# do_an2.net
KiCad netlist of a schematic drawn in Altium Designer
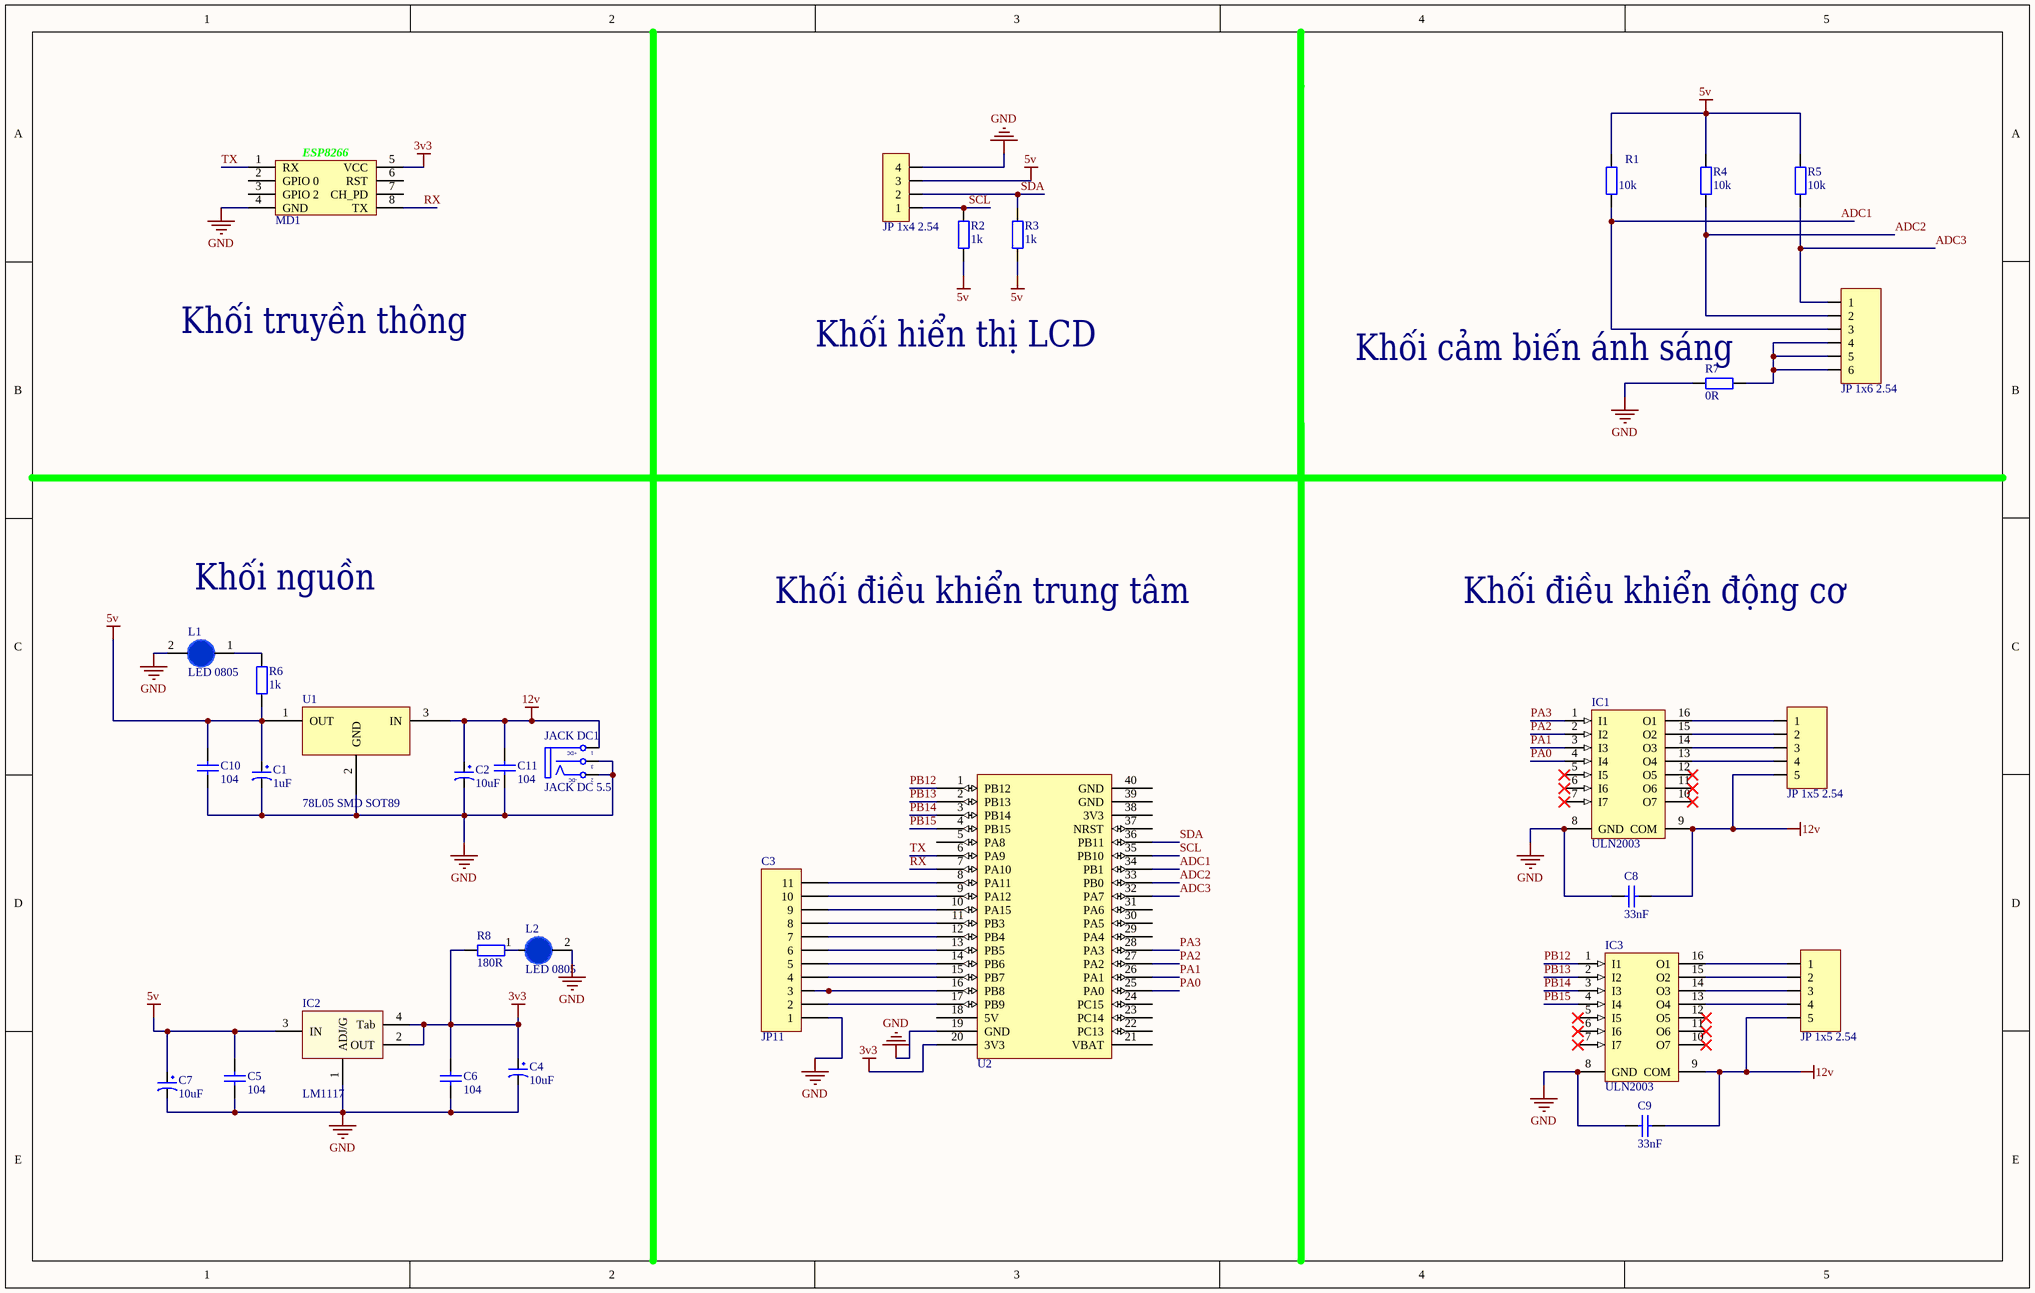
[diagram p0: do_an2.SchDoc]

(export (version "E")
  (design (tool "Eeschema 10.0.6"))
  (components
    (comp (ref "C1")
      (value "1uF")
      (footprint "tu hoa 5mm")
      (description "Cắm")
      (libsource (lib "Altium_Lib_by_KhueNguyenCreator") (part "Tu Hoa 1uF 50V 5x11"))
    )
    (comp (ref "C2")
      (value "10uF")
      (footprint "tu hoa 4mm")
      (description "Cắm")
      (libsource (lib "Altium_Lib_by_KhueNguyenCreator") (part "Tu Hoa 10uF 16V 4x7"))
    )
    (comp (ref "C3")
      (value "JP11")
      (footprint "JP11-C1T")
      (description "WR-PHD 2.54 mm Angled Socket Header")
      (fields
        (field (name "MANUFACTURER") "Würth Elektronik eiSos GmbH")
        (field (name "PARTNO") "613011143121")
        (field (name "CREATED BY") "Karrer Zheng")
      )
      (libsource (lib "My Library") (part "JP11"))
    )
    (comp (ref "C4")
      (value "10uF")
      (footprint "tu hoa 4mm")
      (description "Cắm")
      (libsource (lib "Altium_Lib_by_KhueNguyenCreator") (part "Tu Hoa 10uF 16V 4x7"))
    )
    (comp (ref "C5")
      (value "104")
      (footprint "tu 0805")
      (description "Dán")
      (libsource (lib "Altium_Lib_by_KhueNguyenCreator") (part "Tu 0805 104 50V 10%"))
    )
    (comp (ref "C6")
      (value "104")
      (footprint "tu 0805")
      (description "Dán")
      (libsource (lib "Altium_Lib_by_KhueNguyenCreator") (part "Tu 0805 104 50V 10%"))
    )
    (comp (ref "C7")
      (value "10uF")
      (footprint "tu hoa 4mm")
      (description "Cắm")
      (libsource (lib "Altium_Lib_by_KhueNguyenCreator") (part "Tu Hoa 10uF 16V 4x7"))
    )
    (comp (ref "C8")
      (value "33nF")
      (footprint "tu 0805")
      (description "Dán")
      (libsource (lib "Altium_Lib_by_KhueNguyenCreator") (part "Tu 0805 33nF 50V 20%"))
    )
    (comp (ref "C9")
      (value "33nF")
      (footprint "tu 0805")
      (description "Dán")
      (libsource (lib "Altium_Lib_by_KhueNguyenCreator") (part "Tu 0805 33nF 50V 20%"))
    )
    (comp (ref "C10")
      (value "104")
      (footprint "tu 0805")
      (description "Dán")
      (libsource (lib "Altium_Lib_by_KhueNguyenCreator") (part "Tu 0805 104 50V 10%"))
    )
    (comp (ref "C11")
      (value "104")
      (footprint "tu 0805")
      (description "Dán")
      (libsource (lib "Altium_Lib_by_KhueNguyenCreator") (part "Tu 0805 104 50V 10%"))
    )
    (comp (ref "IC1")
      (value "ULN2003")
      (footprint "SOP 16")
      (description "Dán")
      (libsource (lib "Altium_Lib_by_KhueNguyenCreator") (part "ULN2003A SMD"))
    )
    (comp (ref "IC2")
      (value "LM1117")
      (footprint "SOT223-4N")
      (description "3v3")
      (libsource (lib "My Library") (part "LM1117"))
    )
    (comp (ref "IC3")
      (value "ULN2003")
      (footprint "SOP 16")
      (description "Dán")
      (libsource (lib "Altium_Lib_by_KhueNguyenCreator") (part "ULN2003A SMD"))
    )
    (comp (ref "JACK DC1")
      (value "JACK DC 5.5")
      (footprint "JACK DC 5.5")
      (libsource (lib "Altium_Lib_by_KhueNguyenCreator") (part "JACK DC 5.5"))
    )
    (comp (ref "JP1")
      (value "JP 1x4 2.54")
      (footprint "JP 1x4 CC")
      (description "Cắm")
      (libsource (lib "Altium_Lib_by_KhueNguyenCreator") (part "JP 1x4 2.54 Cai Cong"))
    )
    (comp (ref "JP2")
      (value "JP 1x6 2.54")
      (footprint "JP 1x6 CT")
      (description "Cắm")
      (libsource (lib "Altium_Lib_by_KhueNguyenCreator") (part "JP 1x6 2.54 Cai Thang"))
    )
    (comp (ref "JP3")
      (value "JP 1x5 2.54")
      (footprint "JP 1x5 DT")
      (description "Cắm")
      (libsource (lib "Altium_Lib_by_KhueNguyenCreator") (part "JP 1x5 2.54 Duc Thang"))
    )
    (comp (ref "JP4")
      (value "JP 1x5 2.54")
      (footprint "JP 1x5 DT")
      (description "Cắm")
      (libsource (lib "Altium_Lib_by_KhueNguyenCreator") (part "JP 1x5 2.54 Duc Thang"))
    )
    (comp (ref "L1")
      (value "LED 0805")
      (footprint "LED-0805-Blue")
      (description "Dán")
      (libsource (lib "Altium_Lib_by_KhueNguyenCreator") (part "LED 0805 Xanh Duong"))
    )
    (comp (ref "L2")
      (value "LED 0805")
      (footprint "LED-0805-Blue")
      (description "Dán")
      (libsource (lib "Altium_Lib_by_KhueNguyenCreator") (part "LED 0805 Xanh Duong"))
    )
    (comp (ref "MD1")
      (value "ESP8266 Module")
      (footprint "ESP2866 Module")
      (libsource (lib "Altium_Lib_by_KhueNguyenCreator") (part "ESP8266 Module"))
    )
    (comp (ref "R1")
      (value "10k")
      (footprint "tro smd 0805")
      (description "Dán")
      (libsource (lib "Altium_Lib_by_KhueNguyenCreator") (part "Tro 0805 5% 10k"))
    )
    (comp (ref "R2")
      (value "1k")
      (footprint "tro smd 0805")
      (description "Dán")
      (libsource (lib "Altium_Lib_by_KhueNguyenCreator") (part "Tro 0805 1% 1k"))
    )
    (comp (ref "R3")
      (value "1k")
      (footprint "tro smd 0805")
      (description "Dán")
      (libsource (lib "Altium_Lib_by_KhueNguyenCreator") (part "Tro 0805 1% 1k"))
    )
    (comp (ref "R4")
      (value "10k")
      (footprint "tro smd 0805")
      (description "Dán")
      (libsource (lib "Altium_Lib_by_KhueNguyenCreator") (part "Tro 0805 5% 10k"))
    )
    (comp (ref "R5")
      (value "10k")
      (footprint "tro smd 0805")
      (description "Dán")
      (libsource (lib "Altium_Lib_by_KhueNguyenCreator") (part "Tro 0805 5% 10k"))
    )
    (comp (ref "R6")
      (value "1k")
      (footprint "tro smd 0805")
      (description "Dán")
      (libsource (lib "Altium_Lib_by_KhueNguyenCreator") (part "Tro 0805 5% 1k"))
    )
    (comp (ref "R7")
      (value "0R")
      (footprint "tro smd 0805")
      (description "Dán")
      (libsource (lib "Altium_Lib_by_KhueNguyenCreator") (part "Tro 0805 5% 0R"))
    )
    (comp (ref "R8")
      (value "180R")
      (footprint "tro smd 0805")
      (description "Dán")
      (libsource (lib "Altium_Lib_by_KhueNguyenCreator") (part "Tro 0805 5% 180R"))
    )
    (comp (ref "U1")
      (value "78L05 SMD SOT89")
      (footprint "SOT89")
      (description "Dán")
      (libsource (lib "Altium_Lib_by_KhueNguyenCreator") (part "78L05 SMD SOT89"))
    )
    (comp (ref "U2")
      (value "STM32 BluePill")
      (footprint "STM32 Bluepill")
      (description "STM32F103C8T6 breakout board")
      (libsource (lib "My Library") (part "STM32 BluePill"))
    )
  )
  (nets
    (net (code "1") (name "/ADC1") (class "Default")
      (node (ref "JP2") (pin "3") (pinfunction "3_3") (pintype "passive"))
      (node (ref "R1") (pin "1") (pinfunction "1_1") (pintype "passive"))
      (node (ref "U2") (pin "34") (pinfunction "PB1_34") (pintype "bidirectional"))
    )
    (net (code "2") (name "/ADC2") (class "Default")
      (node (ref "JP2") (pin "2") (pinfunction "2_2") (pintype "passive"))
      (node (ref "R4") (pin "1") (pinfunction "1_1") (pintype "passive"))
      (node (ref "U2") (pin "33") (pinfunction "PB0_33") (pintype "bidirectional"))
    )
    (net (code "3") (name "/ADC3") (class "Default")
      (node (ref "JP2") (pin "1") (pinfunction "1_1") (pintype "passive"))
      (node (ref "R5") (pin "1") (pinfunction "1_1") (pintype "passive"))
      (node (ref "U2") (pin "32") (pinfunction "PA7_32") (pintype "bidirectional"))
    )
    (net (code "4") (name "/PA0") (class "Default")
      (node (ref "IC1") (pin "4") (pinfunction "I4_4") (pintype "input"))
      (node (ref "U2") (pin "25") (pinfunction "PA0_25") (pintype "bidirectional"))
    )
    (net (code "5") (name "/PA1") (class "Default")
      (node (ref "IC1") (pin "3") (pinfunction "I3_3") (pintype "input"))
      (node (ref "U2") (pin "26") (pinfunction "PA1_26") (pintype "bidirectional"))
    )
    (net (code "6") (name "/PA2") (class "Default")
      (node (ref "IC1") (pin "2") (pinfunction "I2_2") (pintype "input"))
      (node (ref "U2") (pin "27") (pinfunction "PA2_27") (pintype "bidirectional"))
    )
    (net (code "7") (name "/PA3") (class "Default")
      (node (ref "IC1") (pin "1") (pinfunction "I1_1") (pintype "input"))
      (node (ref "U2") (pin "28") (pinfunction "PA3_28") (pintype "bidirectional"))
    )
    (net (code "8") (name "/PB12") (class "Default")
      (node (ref "IC3") (pin "1") (pinfunction "I1_1") (pintype "input"))
      (node (ref "U2") (pin "1") (pinfunction "PB12_1") (pintype "bidirectional"))
    )
    (net (code "9") (name "/PB13") (class "Default")
      (node (ref "IC3") (pin "2") (pinfunction "I2_2") (pintype "input"))
      (node (ref "U2") (pin "2") (pinfunction "PB13_2") (pintype "bidirectional"))
    )
    (net (code "10") (name "/PB14") (class "Default")
      (node (ref "IC3") (pin "3") (pinfunction "I3_3") (pintype "input"))
      (node (ref "U2") (pin "3") (pinfunction "PB14_3") (pintype "bidirectional"))
    )
    (net (code "11") (name "/PB15") (class "Default")
      (node (ref "IC3") (pin "4") (pinfunction "I4_4") (pintype "input"))
      (node (ref "U2") (pin "4") (pinfunction "PB15_4") (pintype "bidirectional"))
    )
    (net (code "12") (name "/RX") (class "Default")
      (node (ref "MD1") (pin "8") (pinfunction "TX_8") (pintype "passive"))
      (node (ref "U2") (pin "7") (pinfunction "PA10_7") (pintype "bidirectional"))
    )
    (net (code "13") (name "/SCL") (class "Default")
      (node (ref "JP1") (pin "1") (pinfunction "1_1") (pintype "passive"))
      (node (ref "R2") (pin "2") (pinfunction "2_2") (pintype "passive"))
      (node (ref "U2") (pin "35") (pinfunction "PB10_35") (pintype "bidirectional"))
    )
    (net (code "14") (name "/SDA") (class "Default")
      (node (ref "JP1") (pin "2") (pinfunction "2_2") (pintype "passive"))
      (node (ref "R3") (pin "2") (pinfunction "2_2") (pintype "passive"))
      (node (ref "U2") (pin "36") (pinfunction "PB11_36") (pintype "bidirectional"))
    )
    (net (code "15") (name "/TX") (class "Default")
      (node (ref "MD1") (pin "1") (pinfunction "RX_1") (pintype "passive"))
      (node (ref "U2") (pin "6") (pinfunction "PA9_6") (pintype "bidirectional"))
    )
    (net (code "16") (name "3v3") (class "Default")
      (node (ref "C4") (pin "1") (pinfunction "1_1") (pintype "passive"))
      (node (ref "C6") (pin "1") (pinfunction "1_1") (pintype "passive"))
      (node (ref "IC2") (pin "2") (pinfunction "OUT_2") (pintype "passive"))
      (node (ref "IC2") (pin "4") (pinfunction "Tab_4") (pintype "passive"))
      (node (ref "MD1") (pin "5") (pinfunction "VCC_5") (pintype "passive"))
      (node (ref "R8") (pin "1") (pinfunction "1_1") (pintype "passive"))
      (node (ref "U2") (pin "20") (pinfunction "3V3_20") (pintype "power_in"))
    )
    (net (code "17") (name "5v") (class "Default")
      (node (ref "C1") (pin "1") (pinfunction "1_1") (pintype "passive"))
      (node (ref "C10") (pin "1") (pinfunction "1_1") (pintype "passive"))
      (node (ref "C5") (pin "1") (pinfunction "1_1") (pintype "passive"))
      (node (ref "C7") (pin "1") (pinfunction "1_1") (pintype "passive"))
      (node (ref "IC2") (pin "3") (pinfunction "IN_3") (pintype "passive"))
      (node (ref "JP1") (pin "3") (pinfunction "3_3") (pintype "passive"))
      (node (ref "R1") (pin "2") (pinfunction "2_2") (pintype "passive"))
      (node (ref "R2") (pin "1") (pinfunction "1_1") (pintype "passive"))
      (node (ref "R3") (pin "1") (pinfunction "1_1") (pintype "passive"))
      (node (ref "R4") (pin "2") (pinfunction "2_2") (pintype "passive"))
      (node (ref "R5") (pin "2") (pinfunction "2_2") (pintype "passive"))
      (node (ref "R6") (pin "2") (pinfunction "2_2") (pintype "passive"))
      (node (ref "U1") (pin "1") (pinfunction "OUT_1") (pintype "passive"))
    )
    (net (code "18") (name "12v") (class "Default")
      (node (ref "C11") (pin "1") (pinfunction "1_1") (pintype "passive"))
      (node (ref "C2") (pin "1") (pinfunction "1_1") (pintype "passive"))
      (node (ref "C8") (pin "1") (pinfunction "1_1") (pintype "passive"))
      (node (ref "C9") (pin "1") (pinfunction "1_1") (pintype "passive"))
      (node (ref "IC1") (pin "9") (pinfunction "COM_9") (pintype "passive"))
      (node (ref "IC3") (pin "9") (pinfunction "COM_9") (pintype "passive"))
      (node (ref "JACK DC1") (pin "1") (pinfunction "T_1") (pintype "passive"))
      (node (ref "JP3") (pin "5") (pinfunction "5_5") (pintype "passive"))
      (node (ref "JP4") (pin "5") (pinfunction "5_5") (pintype "passive"))
      (node (ref "U1") (pin "3") (pinfunction "IN_3") (pintype "passive"))
    )
    (net (code "19") (name "GND") (class "Default")
      (node (ref "C1") (pin "2") (pinfunction "2_2") (pintype "passive"))
      (node (ref "C10") (pin "2") (pinfunction "2_2") (pintype "passive"))
      (node (ref "C11") (pin "2") (pinfunction "2_2") (pintype "passive"))
      (node (ref "C2") (pin "2") (pinfunction "2_2") (pintype "passive"))
      (node (ref "C3") (pin "1") (pinfunction "1_1") (pintype "passive"))
      (node (ref "C4") (pin "2") (pinfunction "2_2") (pintype "passive"))
      (node (ref "C5") (pin "2") (pinfunction "2_2") (pintype "passive"))
      (node (ref "C6") (pin "2") (pinfunction "2_2") (pintype "passive"))
      (node (ref "C7") (pin "2") (pinfunction "2_2") (pintype "passive"))
      (node (ref "C8") (pin "2") (pinfunction "2_2") (pintype "passive"))
      (node (ref "C9") (pin "2") (pinfunction "2_2") (pintype "passive"))
      (node (ref "IC1") (pin "8") (pinfunction "GND_8") (pintype "power_in"))
      (node (ref "IC2") (pin "1") (pinfunction "ADJ/G_1") (pintype "passive"))
      (node (ref "IC3") (pin "8") (pinfunction "GND_8") (pintype "power_in"))
      (node (ref "JACK DC1") (pin "2") (pinfunction "TN_2") (pintype "passive"))
      (node (ref "JACK DC1") (pin "3") (pinfunction "S_3") (pintype "power_in"))
      (node (ref "JP1") (pin "4") (pinfunction "4_4") (pintype "passive"))
      (node (ref "L1") (pin "2") (pinfunction "K_2") (pintype "passive"))
      (node (ref "L2") (pin "2") (pinfunction "K_2") (pintype "passive"))
      (node (ref "MD1") (pin "4") (pinfunction "GND_4") (pintype "passive"))
      (node (ref "R7") (pin "1") (pinfunction "1_1") (pintype "passive"))
      (node (ref "U1") (pin "2") (pinfunction "GND_2") (pintype "passive"))
      (node (ref "U2") (pin "19") (pinfunction "GND_19") (pintype "power_in"))
    )
    (net (code "20") (name "Net-(IC1-O1)") (class "Default")
      (node (ref "IC1") (pin "16") (pinfunction "O1_16") (pintype "open_collector"))
      (node (ref "JP3") (pin "1") (pinfunction "1_1") (pintype "passive"))
    )
    (net (code "21") (name "Net-(IC1-O2)") (class "Default")
      (node (ref "IC1") (pin "15") (pinfunction "O2_15") (pintype "open_collector"))
      (node (ref "JP3") (pin "2") (pinfunction "2_2") (pintype "passive"))
    )
    (net (code "22") (name "Net-(IC1-O3)") (class "Default")
      (node (ref "IC1") (pin "14") (pinfunction "O3_14") (pintype "open_collector"))
      (node (ref "JP3") (pin "3") (pinfunction "3_3") (pintype "passive"))
    )
    (net (code "23") (name "Net-(IC1-O4)") (class "Default")
      (node (ref "IC1") (pin "13") (pinfunction "O4_13") (pintype "open_collector"))
      (node (ref "JP3") (pin "4") (pinfunction "4_4") (pintype "passive"))
    )
    (net (code "24") (name "Net-(IC3-O1)") (class "Default")
      (node (ref "IC3") (pin "16") (pinfunction "O1_16") (pintype "open_collector"))
      (node (ref "JP4") (pin "1") (pinfunction "1_1") (pintype "passive"))
    )
    (net (code "25") (name "Net-(IC3-O2)") (class "Default")
      (node (ref "IC3") (pin "15") (pinfunction "O2_15") (pintype "open_collector"))
      (node (ref "JP4") (pin "2") (pinfunction "2_2") (pintype "passive"))
    )
    (net (code "26") (name "Net-(IC3-O3)") (class "Default")
      (node (ref "IC3") (pin "14") (pinfunction "O3_14") (pintype "open_collector"))
      (node (ref "JP4") (pin "3") (pinfunction "3_3") (pintype "passive"))
    )
    (net (code "27") (name "Net-(IC3-O4)") (class "Default")
      (node (ref "IC3") (pin "13") (pinfunction "O4_13") (pintype "open_collector"))
      (node (ref "JP4") (pin "4") (pinfunction "4_4") (pintype "passive"))
    )
    (net (code "28") (name "Net-(JP2-Pad4)") (class "Default")
      (node (ref "JP2") (pin "4") (pinfunction "4_4") (pintype "passive"))
      (node (ref "JP2") (pin "5") (pinfunction "5_5") (pintype "passive"))
      (node (ref "JP2") (pin "6") (pinfunction "6_6") (pintype "passive"))
      (node (ref "R7") (pin "2") (pinfunction "2_2") (pintype "passive"))
    )
    (net (code "29") (name "Net-(L1-A)") (class "Default")
      (node (ref "L1") (pin "1") (pinfunction "A_1") (pintype "passive"))
      (node (ref "R6") (pin "1") (pinfunction "1_1") (pintype "passive"))
    )
    (net (code "30") (name "Net-(L2-A)") (class "Default")
      (node (ref "L2") (pin "1") (pinfunction "A_1") (pintype "passive"))
      (node (ref "R8") (pin "2") (pinfunction "2_2") (pintype "passive"))
    )
    (net (code "31") (name "Net-(U2-PA11)") (class "Default")
      (node (ref "C3") (pin "11") (pinfunction "11_11") (pintype "passive"))
      (node (ref "U2") (pin "8") (pinfunction "PA11_8") (pintype "bidirectional"))
    )
    (net (code "32") (name "Net-(U2-PA12)") (class "Default")
      (node (ref "C3") (pin "10") (pinfunction "10_10") (pintype "passive"))
      (node (ref "U2") (pin "9") (pinfunction "PA12_9") (pintype "bidirectional"))
    )
    (net (code "33") (name "Net-(U2-PA15)") (class "Default")
      (node (ref "C3") (pin "9") (pinfunction "9_9") (pintype "passive"))
      (node (ref "U2") (pin "10") (pinfunction "PA15_10") (pintype "bidirectional"))
    )
    (net (code "34") (name "Net-(U2-PB3)") (class "Default")
      (node (ref "C3") (pin "8") (pinfunction "8_8") (pintype "passive"))
      (node (ref "U2") (pin "11") (pinfunction "PB3_11") (pintype "bidirectional"))
    )
    (net (code "35") (name "Net-(U2-PB4)") (class "Default")
      (node (ref "C3") (pin "7") (pinfunction "7_7") (pintype "passive"))
      (node (ref "U2") (pin "12") (pinfunction "PB4_12") (pintype "bidirectional"))
    )
    (net (code "36") (name "Net-(U2-PB5)") (class "Default")
      (node (ref "C3") (pin "6") (pinfunction "6_6") (pintype "passive"))
      (node (ref "U2") (pin "13") (pinfunction "PB5_13") (pintype "bidirectional"))
    )
    (net (code "37") (name "Net-(U2-PB6)") (class "Default")
      (node (ref "C3") (pin "5") (pinfunction "5_5") (pintype "passive"))
      (node (ref "U2") (pin "14") (pinfunction "PB6_14") (pintype "bidirectional"))
    )
    (net (code "38") (name "Net-(U2-PB7)") (class "Default")
      (node (ref "C3") (pin "4") (pinfunction "4_4") (pintype "passive"))
      (node (ref "U2") (pin "15") (pinfunction "PB7_15") (pintype "bidirectional"))
    )
    (net (code "39") (name "Net-(U2-PB8)") (class "Default")
      (node (ref "C3") (pin "3") (pinfunction "3_3") (pintype "passive"))
      (node (ref "U2") (pin "16") (pinfunction "PB8_16") (pintype "bidirectional"))
    )
    (net (code "40") (name "Net-(U2-PB9)") (class "Default")
      (node (ref "C3") (pin "2") (pinfunction "2_2") (pintype "passive"))
      (node (ref "U2") (pin "17") (pinfunction "PB9_17") (pintype "bidirectional"))
    )
    (net (code "41") (name "unconnected-(IC1-I5-Pad5)") (class "Default")
      (node (ref "IC1") (pin "5") (pinfunction "I5_5") (pintype "input+no_connect"))
    )
    (net (code "42") (name "unconnected-(IC1-I6-Pad6)") (class "Default")
      (node (ref "IC1") (pin "6") (pinfunction "I6_6") (pintype "input+no_connect"))
    )
    (net (code "43") (name "unconnected-(IC1-I7-Pad7)") (class "Default")
      (node (ref "IC1") (pin "7") (pinfunction "I7_7") (pintype "input+no_connect"))
    )
    (net (code "44") (name "unconnected-(IC1-O5-Pad12)") (class "Default")
      (node (ref "IC1") (pin "12") (pinfunction "O5_12") (pintype "open_collector+no_connect"))
    )
    (net (code "45") (name "unconnected-(IC1-O6-Pad11)") (class "Default")
      (node (ref "IC1") (pin "11") (pinfunction "O6_11") (pintype "open_collector+no_connect"))
    )
    (net (code "46") (name "unconnected-(IC1-O7-Pad10)") (class "Default")
      (node (ref "IC1") (pin "10") (pinfunction "O7_10") (pintype "open_collector+no_connect"))
    )
    (net (code "47") (name "unconnected-(IC3-I5-Pad5)") (class "Default")
      (node (ref "IC3") (pin "5") (pinfunction "I5_5") (pintype "input+no_connect"))
    )
    (net (code "48") (name "unconnected-(IC3-I6-Pad6)") (class "Default")
      (node (ref "IC3") (pin "6") (pinfunction "I6_6") (pintype "input+no_connect"))
    )
    (net (code "49") (name "unconnected-(IC3-I7-Pad7)") (class "Default")
      (node (ref "IC3") (pin "7") (pinfunction "I7_7") (pintype "input+no_connect"))
    )
    (net (code "50") (name "unconnected-(IC3-O5-Pad12)") (class "Default")
      (node (ref "IC3") (pin "12") (pinfunction "O5_12") (pintype "open_collector+no_connect"))
    )
    (net (code "51") (name "unconnected-(IC3-O6-Pad11)") (class "Default")
      (node (ref "IC3") (pin "11") (pinfunction "O6_11") (pintype "open_collector+no_connect"))
    )
    (net (code "52") (name "unconnected-(IC3-O7-Pad10)") (class "Default")
      (node (ref "IC3") (pin "10") (pinfunction "O7_10") (pintype "open_collector+no_connect"))
    )
    (net (code "53") (name "unconnected-(MD1-CH_PD-Pad7)") (class "Default")
      (node (ref "MD1") (pin "7") (pinfunction "CH_PD_7") (pintype "passive"))
    )
    (net (code "54") (name "unconnected-(MD1-GPIO_0-Pad2)") (class "Default")
      (node (ref "MD1") (pin "2") (pinfunction "GPIO_0_2") (pintype "passive"))
    )
    (net (code "55") (name "unconnected-(MD1-GPIO_2-Pad3)") (class "Default")
      (node (ref "MD1") (pin "3") (pinfunction "GPIO_2_3") (pintype "passive"))
    )
    (net (code "56") (name "unconnected-(MD1-RST-Pad6)") (class "Default")
      (node (ref "MD1") (pin "6") (pinfunction "RST_6") (pintype "passive"))
    )
    (net (code "57") (name "unconnected-(U2-3V3-Pad38)") (class "Default")
      (node (ref "U2") (pin "38") (pinfunction "3V3_38") (pintype "power_in"))
    )
    (net (code "58") (name "unconnected-(U2-5V-Pad18)") (class "Default")
      (node (ref "U2") (pin "18") (pinfunction "5V_18") (pintype "power_in"))
    )
    (net (code "59") (name "unconnected-(U2-GND-Pad39)") (class "Default")
      (node (ref "U2") (pin "39") (pinfunction "GND_39") (pintype "power_in"))
    )
    (net (code "60") (name "unconnected-(U2-GND-Pad40)") (class "Default")
      (node (ref "U2") (pin "40") (pinfunction "GND_40") (pintype "power_in"))
    )
    (net (code "61") (name "unconnected-(U2-NRST-Pad37)") (class "Default")
      (node (ref "U2") (pin "37") (pinfunction "NRST_37") (pintype "bidirectional"))
    )
    (net (code "62") (name "unconnected-(U2-PA4-Pad29)") (class "Default")
      (node (ref "U2") (pin "29") (pinfunction "PA4_29") (pintype "bidirectional"))
    )
    (net (code "63") (name "unconnected-(U2-PA5-Pad30)") (class "Default")
      (node (ref "U2") (pin "30") (pinfunction "PA5_30") (pintype "bidirectional"))
    )
    (net (code "64") (name "unconnected-(U2-PA6-Pad31)") (class "Default")
      (node (ref "U2") (pin "31") (pinfunction "PA6_31") (pintype "bidirectional"))
    )
    (net (code "65") (name "unconnected-(U2-PA8-Pad5)") (class "Default")
      (node (ref "U2") (pin "5") (pinfunction "PA8_5") (pintype "bidirectional"))
    )
    (net (code "66") (name "unconnected-(U2-PC13-Pad22)") (class "Default")
      (node (ref "U2") (pin "22") (pinfunction "PC13_22") (pintype "bidirectional"))
    )
    (net (code "67") (name "unconnected-(U2-PC14-Pad23)") (class "Default")
      (node (ref "U2") (pin "23") (pinfunction "PC14_23") (pintype "bidirectional"))
    )
    (net (code "68") (name "unconnected-(U2-PC15-Pad24)") (class "Default")
      (node (ref "U2") (pin "24") (pinfunction "PC15_24") (pintype "bidirectional"))
    )
    (net (code "69") (name "unconnected-(U2-VBAT-Pad21)") (class "Default")
      (node (ref "U2") (pin "21") (pinfunction "VBAT_21") (pintype "power_in"))
    )
  )
)
